# SCH_Flight-Computer-V5_2024-08-19.net
KiCad netlist of a schematic drawn in EasyEDA
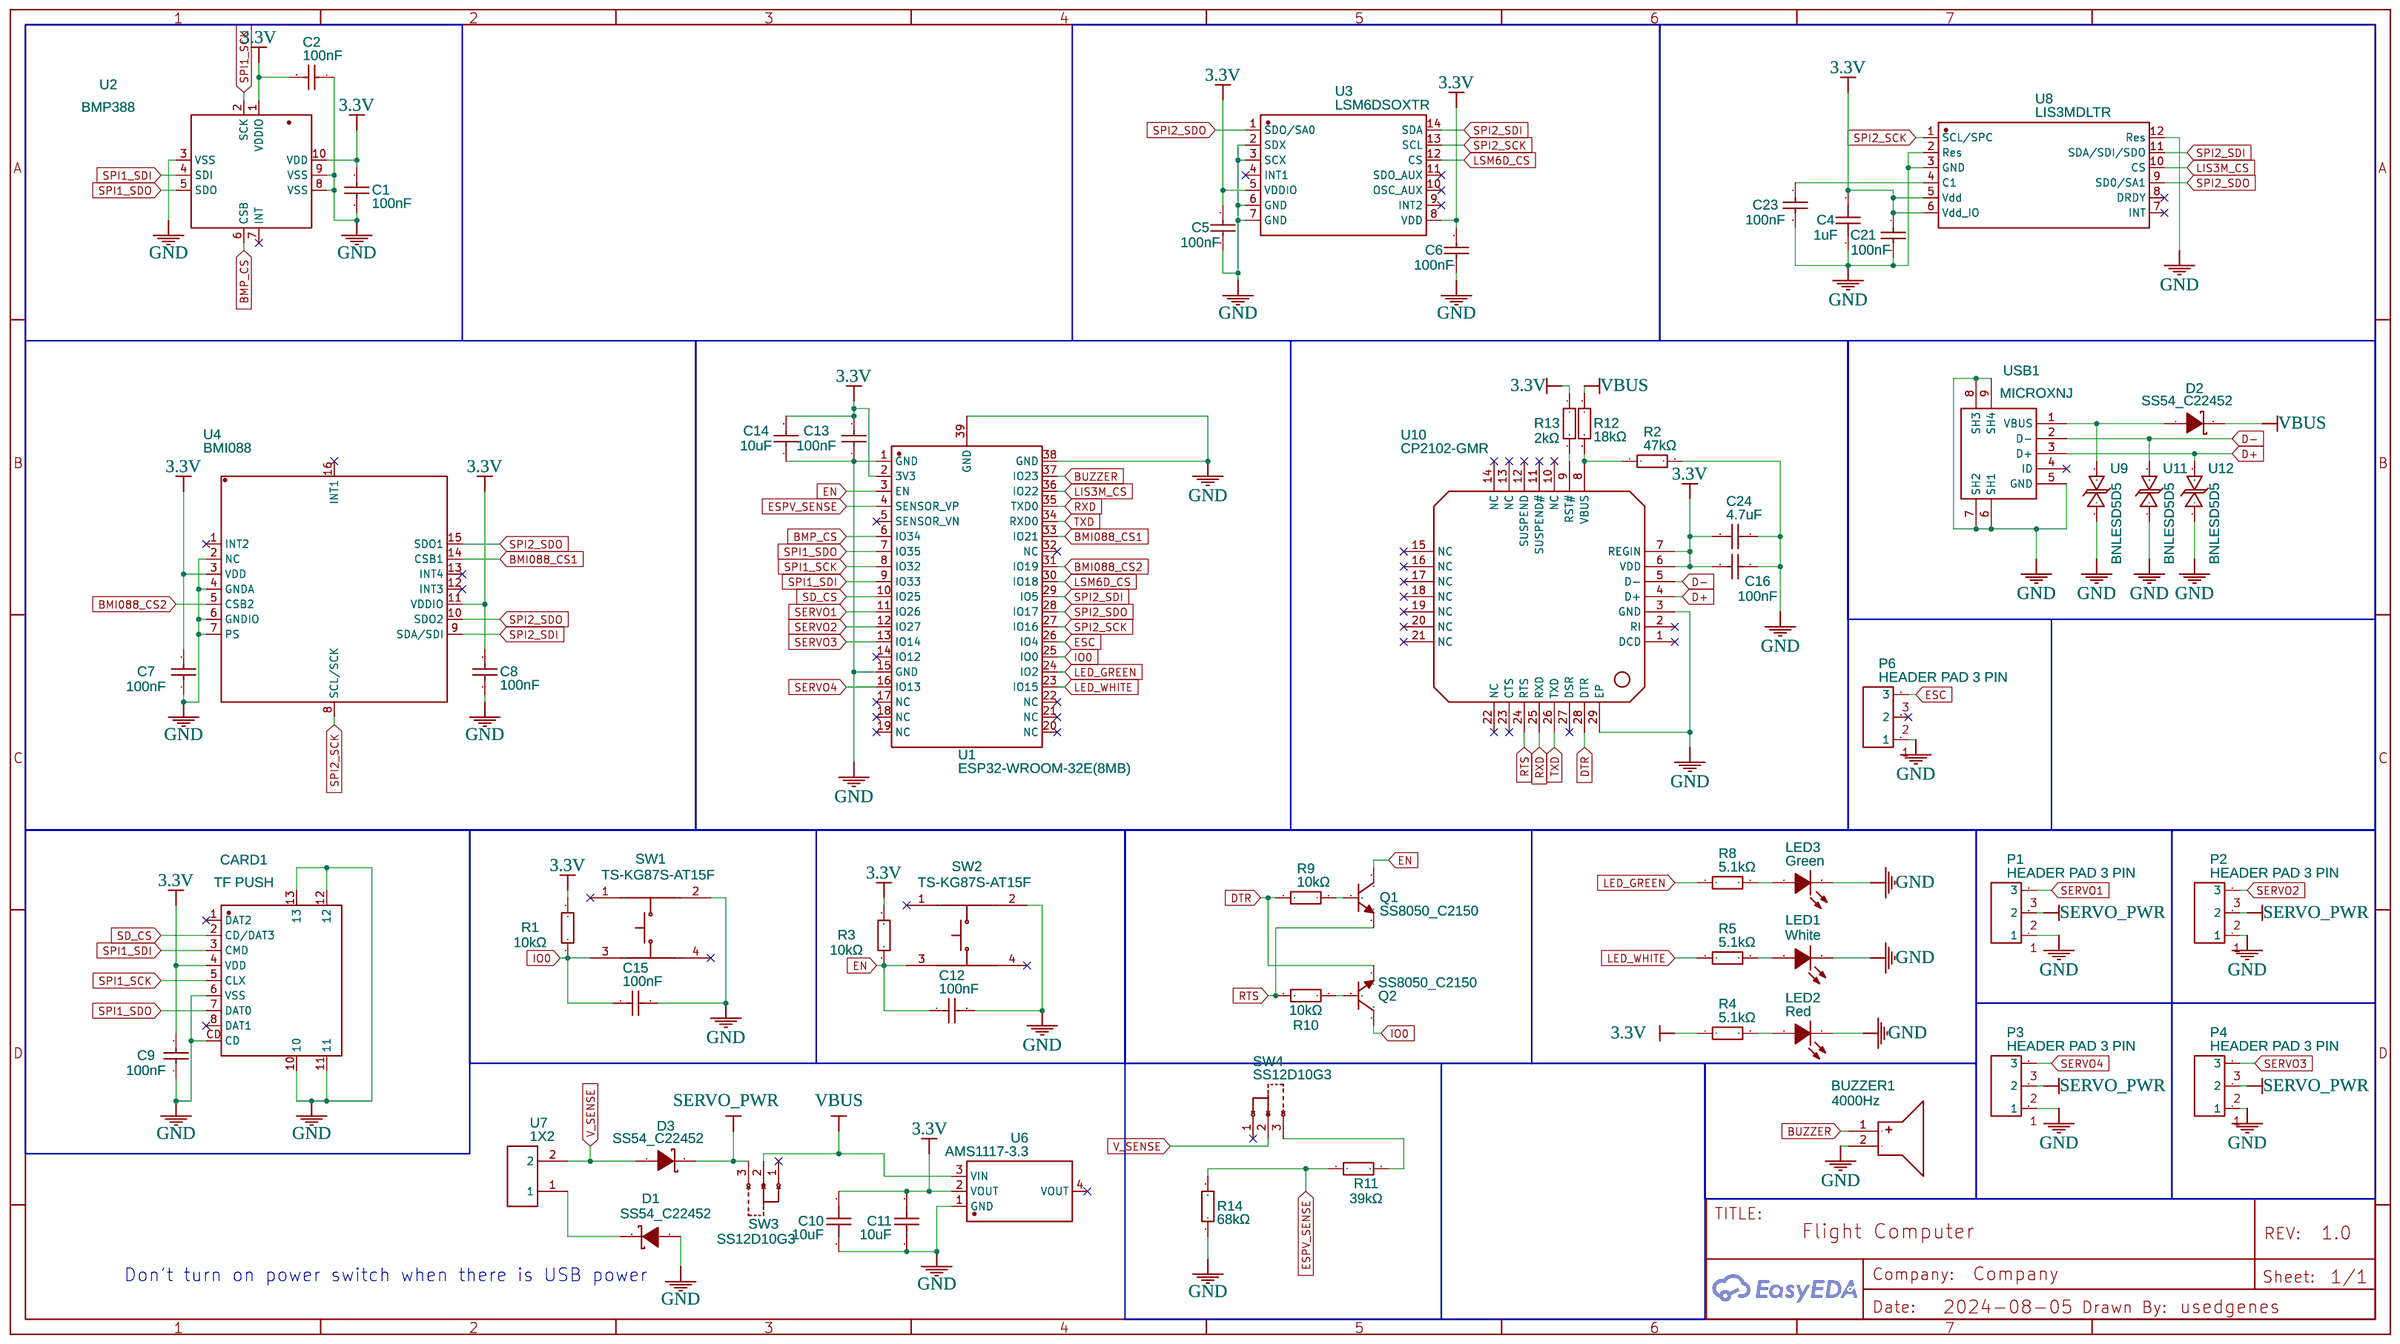
[diagram p0: schematic sheet]

(export (version "E")
  (design (tool "Eeschema 10.0.6"))
  (components
    (comp (ref "BUZZER1")
      (value "4000Hz")
      (fields
        (field (name "Manufacturer Part") "SKY-1475-0540-45P7.6")
        (field (name "Manufacturer") "S&S(海旭)")
      )
      (libsource (lib "") (part "SKY-1475-0540-45P7.6"))
    )
    (comp (ref "C1")
      (value "100nF")
      (fields
        (field (name "Manufacturer Part") "CL05B104KO5NNNC")
        (field (name "Manufacturer") "SAMSUNG(三星)")
      )
      (libsource (lib "") (part "CL05B104KO5NNNC_1"))
    )
    (comp (ref "C2")
      (value "100nF")
      (fields
        (field (name "Manufacturer Part") "CL05B104KO5NNNC")
        (field (name "Manufacturer") "SAMSUNG(三星)")
      )
      (libsource (lib "") (part "CL05B104KO5NNNC_2"))
    )
    (comp (ref "C4")
      (value "1uF")
      (fields
        (field (name "Manufacturer Part") "CL05A105KA5NQNC")
        (field (name "Manufacturer") "SAMSUNG(三星)")
      )
      (libsource (lib "") (part "CL05A105KA5NQNC"))
    )
    (comp (ref "C5")
      (value "100nF")
      (fields
        (field (name "Manufacturer Part") "CL05B104KO5NNNC")
        (field (name "Manufacturer") "SAMSUNG(三星)")
      )
      (libsource (lib "") (part "CL05B104KO5NNNC_1"))
    )
    (comp (ref "C6")
      (value "100nF")
      (fields
        (field (name "Manufacturer Part") "CL05B104KO5NNNC")
        (field (name "Manufacturer") "SAMSUNG(三星)")
      )
      (libsource (lib "") (part "CL05B104KO5NNNC_1"))
    )
    (comp (ref "C7")
      (value "100nF")
      (fields
        (field (name "Manufacturer Part") "CL05B104KO5NNNC")
        (field (name "Manufacturer") "SAMSUNG(三星)")
      )
      (libsource (lib "") (part "CL05B104KO5NNNC_1"))
    )
    (comp (ref "C8")
      (value "100nF")
      (fields
        (field (name "Manufacturer Part") "CL05B104KO5NNNC")
        (field (name "Manufacturer") "SAMSUNG(三星)")
      )
      (libsource (lib "") (part "CL05B104KO5NNNC_1"))
    )
    (comp (ref "C9")
      (value "100nF")
      (fields
        (field (name "Manufacturer Part") "CL05B104KO5NNNC")
        (field (name "Manufacturer") "SAMSUNG(三星)")
      )
      (libsource (lib "") (part "CL05B104KO5NNNC_1"))
    )
    (comp (ref "C10")
      (value "10uF")
      (fields
        (field (name "Manufacturer Part") "CL10A106KP8NNNC")
        (field (name "Manufacturer") "SAMSUNG(三星)")
      )
      (libsource (lib "") (part "CL10A106KP8NNNC"))
    )
    (comp (ref "C11")
      (value "10uF")
      (fields
        (field (name "Manufacturer Part") "CL10A106KP8NNNC")
        (field (name "Manufacturer") "SAMSUNG(三星)")
      )
      (libsource (lib "") (part "CL10A106KP8NNNC"))
    )
    (comp (ref "C12")
      (value "100nF")
      (fields
        (field (name "Manufacturer Part") "CL05B104KO5NNNC")
        (field (name "Manufacturer") "SAMSUNG(三星)")
      )
      (libsource (lib "") (part "CL05B104KO5NNNC"))
    )
    (comp (ref "C13")
      (value "100nF")
      (fields
        (field (name "Manufacturer Part") "CL05B104KO5NNNC")
        (field (name "Manufacturer") "SAMSUNG(三星)")
      )
      (libsource (lib "") (part "CL05B104KO5NNNC_1"))
    )
    (comp (ref "C14")
      (value "10uF")
      (fields
        (field (name "Manufacturer Part") "CL05A106MQ5NUNC")
        (field (name "Manufacturer") "SAMSUNG(三星)")
      )
      (libsource (lib "") (part "CL05A106MQ5NUNC"))
    )
    (comp (ref "C15")
      (value "100nF")
      (fields
        (field (name "Manufacturer Part") "CL05B104KO5NNNC")
        (field (name "Manufacturer") "SAMSUNG(三星)")
      )
      (libsource (lib "") (part "CL05B104KO5NNNC"))
    )
    (comp (ref "C16")
      (value "100nF")
      (fields
        (field (name "Manufacturer Part") "CL05B104KO5NNNC")
        (field (name "Manufacturer") "SAMSUNG(三星)")
      )
      (libsource (lib "") (part "CL05B104KO5NNNC"))
    )
    (comp (ref "C21")
      (value "100nF")
      (fields
        (field (name "Manufacturer Part") "CL05B104KO5NNNC")
        (field (name "Manufacturer") "SAMSUNG(三星)")
      )
      (libsource (lib "") (part "CL05B104KO5NNNC_3"))
    )
    (comp (ref "C23")
      (value "100nF")
      (fields
        (field (name "Manufacturer Part") "CL05B104KO5NNNC")
        (field (name "Manufacturer") "SAMSUNG(三星)")
      )
      (libsource (lib "") (part "CL05B104KO5NNNC_3"))
    )
    (comp (ref "C24")
      (value "4.7uF")
      (fields
        (field (name "Manufacturer Part") "CL05A475MP5NRNC")
        (field (name "Manufacturer") "SAMSUNG(三星)")
      )
      (libsource (lib "") (part "CL05A475MP5NRNC"))
    )
    (comp (ref "CARD1")
      (value "TF PUSH")
      (fields (field (name "Manufacturer") "SHOU HAN(首韩)"))
      (libsource (lib "") (part "TF PUSH"))
    )
    (comp (ref "D1")
      (value "SS54_C22452")
      (fields (field (name "Manufacturer Part") "SS54") (field (name "Manufacturer") "MDD(辰达半导体)"))
      (libsource (lib "") (part "SS54_C22452_1"))
    )
    (comp (ref "D2")
      (value "SS54_C22452")
      (fields (field (name "Manufacturer Part") "SS54") (field (name "Manufacturer") "MDD(辰达半导体)"))
      (libsource (lib "") (part "SS54_C22452"))
    )
    (comp (ref "D3")
      (value "SS54_C22452")
      (fields (field (name "Manufacturer Part") "SS54") (field (name "Manufacturer") "MDD(辰达半导体)"))
      (libsource (lib "") (part "SS54_C22452"))
    )
    (comp (ref "LED1")
      (value "White")
      (fields (field (name "Manufacturer Part") "KT-0603白灯") (field (name "Manufacturer") "KENTO"))
      (libsource (lib "") (part "0603White light_C2290"))
    )
    (comp (ref "LED2")
      (value "Red")
      (fields (field (name "Manufacturer Part") "KT-0603R") (field (name "Manufacturer") "KENTO"))
      (libsource (lib "") (part "KT-0603R"))
    )
    (comp (ref "LED3")
      (value "Green")
      (fields (field (name "Manufacturer Part") "KT-0805G") (field (name "Manufacturer") "KENTO"))
      (libsource (lib "") (part "0805G (Green)"))
    )
    (comp (ref "P1")
      (value "HEADER PAD 3 PIN")
      (fields
        (field (name "Manufacturer Part") "Female headerHDR1X8-2.54")
        (field (name "Manufacturer") "BOOMELE")
      )
      (libsource (lib "") (part "HEADER PAD 3 PIN"))
    )
    (comp (ref "P2")
      (value "HEADER PAD 3 PIN")
      (fields
        (field (name "Manufacturer Part") "Female headerHDR1X8-2.54")
        (field (name "Manufacturer") "BOOMELE")
      )
      (libsource (lib "") (part "HEADER PAD 3 PIN"))
    )
    (comp (ref "P3")
      (value "HEADER PAD 3 PIN")
      (fields
        (field (name "Manufacturer Part") "Female headerHDR1X8-2.54")
        (field (name "Manufacturer") "BOOMELE")
      )
      (libsource (lib "") (part "HEADER PAD 3 PIN"))
    )
    (comp (ref "P4")
      (value "HEADER PAD 3 PIN")
      (fields
        (field (name "Manufacturer Part") "Female headerHDR1X8-2.54")
        (field (name "Manufacturer") "BOOMELE")
      )
      (libsource (lib "") (part "HEADER PAD 3 PIN"))
    )
    (comp (ref "P6")
      (value "HEADER PAD 3 PIN")
      (fields
        (field (name "Manufacturer Part") "Female headerHDR1X8-2.54")
        (field (name "Manufacturer") "BOOMELE")
      )
      (libsource (lib "") (part "HEADER PAD 3 PIN"))
    )
    (comp (ref "Q1")
      (value "SS8050_C2150")
      (fields (field (name "Manufacturer Part") "SS8050") (field (name "Manufacturer") "CJ(江苏长电/长晶)"))
      (libsource (lib "") (part "SS8050_C2150_1"))
    )
    (comp (ref "Q2")
      (value "SS8050_C2150")
      (fields (field (name "Manufacturer Part") "SS8050") (field (name "Manufacturer") "CJ(江苏长电/长晶)"))
      (libsource (lib "") (part "SS8050_C2150"))
    )
    (comp (ref "R1")
      (value "10kΩ")
      (fields
        (field (name "Manufacturer Part") "0603WAF1002T5E")
        (field (name "Manufacturer") "UNI-ROYAL(厚声)")
      )
      (libsource (lib "") (part "0603WAF1002T5E_1"))
    )
    (comp (ref "R2")
      (value "47kΩ")
      (fields
        (field (name "Manufacturer Part") "0402WGF4702TCE")
        (field (name "Manufacturer") "UNI-ROYAL(厚声)")
      )
      (libsource (lib "") (part "0402WGF4702TCE"))
    )
    (comp (ref "R3")
      (value "10kΩ")
      (fields
        (field (name "Manufacturer Part") "0603WAF1002T5E")
        (field (name "Manufacturer") "UNI-ROYAL(厚声)")
      )
      (libsource (lib "") (part "0603WAF1002T5E_1"))
    )
    (comp (ref "R4")
      (value "5.1kΩ")
      (fields
        (field (name "Manufacturer Part") "0402WGF5101TCE")
        (field (name "Manufacturer") "UNI-ROYAL(厚声)")
      )
      (libsource (lib "") (part "0402WGF5101TCE"))
    )
    (comp (ref "R5")
      (value "5.1kΩ")
      (fields
        (field (name "Manufacturer Part") "0402WGF5101TCE")
        (field (name "Manufacturer") "UNI-ROYAL(厚声)")
      )
      (libsource (lib "") (part "0402WGF5101TCE"))
    )
    (comp (ref "R8")
      (value "5.1kΩ")
      (fields
        (field (name "Manufacturer Part") "0402WGF5101TCE")
        (field (name "Manufacturer") "UNI-ROYAL(厚声)")
      )
      (libsource (lib "") (part "0402WGF5101TCE"))
    )
    (comp (ref "R9")
      (value "10kΩ")
      (fields
        (field (name "Manufacturer Part") "0603WAF1002T5E")
        (field (name "Manufacturer") "UNI-ROYAL(厚声)")
      )
      (libsource (lib "") (part "0603WAF1002T5E_2"))
    )
    (comp (ref "R10")
      (value "10kΩ")
      (fields
        (field (name "Manufacturer Part") "0603WAF1002T5E")
        (field (name "Manufacturer") "UNI-ROYAL(厚声)")
      )
      (libsource (lib "") (part "0603WAF1002T5E"))
    )
    (comp (ref "R11")
      (value "39kΩ")
      (fields
        (field (name "Manufacturer Part") "0603WAF3902T5E")
        (field (name "Manufacturer") "UNI-ROYAL(厚声)")
      )
      (libsource (lib "") (part "0603WAF3902T5E"))
    )
    (comp (ref "R12")
      (value "18kΩ")
      (fields
        (field (name "Manufacturer Part") "0603WAF1802T5E")
        (field (name "Manufacturer") "UNI-ROYAL(厚声)")
      )
      (libsource (lib "") (part "0603WAF1802T5E"))
    )
    (comp (ref "R13")
      (value "2kΩ")
      (fields
        (field (name "Manufacturer Part") "0402WGF2001TCE")
        (field (name "Manufacturer") "UNI-ROYAL(厚声)")
      )
      (libsource (lib "") (part "0402WGF2001TCE"))
    )
    (comp (ref "R14")
      (value "68kΩ")
      (fields
        (field (name "Manufacturer Part") "0603WAF6802T5E")
        (field (name "Manufacturer") "UNI-ROYAL(厚声)")
      )
      (libsource (lib "") (part "0603WAF6802T5E"))
    )
    (comp (ref "SW1")
      (value "TS-KG87S-AT15F")
      (fields (field (name "Manufacturer") "HANBO(汉博)"))
      (libsource (lib "") (part "TS-KG87S-AT15F"))
    )
    (comp (ref "SW2")
      (value "TS-KG87S-AT15F")
      (fields (field (name "Manufacturer") "HANBO(汉博)"))
      (libsource (lib "") (part "TS-KG87S-AT15F"))
    )
    (comp (ref "SW3")
      (value "SS12D10G3")
      (fields (field (name "Manufacturer") "SHOU HAN(首韩)"))
      (libsource (lib "") (part "SS12D10G3_1"))
    )
    (comp (ref "SW4")
      (value "SS12D10G3")
      (fields (field (name "Manufacturer") "SHOU HAN(首韩)"))
      (libsource (lib "") (part "SS12D10G3"))
    )
    (comp (ref "U1")
      (value "ESP32-WROOM-32E(8MB)")
      (fields
        (field (name "Manufacturer Part") "ESP32-WROOM-32E-N8")
        (field (name "Manufacturer") "ESPRESSIF(乐鑫)")
      )
      (libsource (lib "") (part "ESP32-WROOM-32E(8MB)"))
    )
    (comp (ref "U2")
      (value "BMP388")
      (fields (field (name "Manufacturer") "Bosch(博世)"))
      (libsource (lib "") (part "BMP388"))
    )
    (comp (ref "U3")
      (value "LSM6DSOXTR")
      (fields (field (name "Manufacturer") "ST(意法半导体)"))
      (libsource (lib "") (part "LSM6DSOXTR"))
    )
    (comp (ref "U4")
      (value "BMI088")
      (fields (field (name "Manufacturer") "Bosch(博世)"))
      (libsource (lib "") (part "BMI088"))
    )
    (comp (ref "U6")
      (value "AMS1117-3.3")
      (fields (field (name "Manufacturer") "AMS"))
      (libsource (lib "") (part "AMS1117-3.3"))
    )
    (comp (ref "U7") (value "1X2") (libsource (lib "") (part "1X2")))
    (comp (ref "U8")
      (value "LIS3MDLTR")
      (fields (field (name "Manufacturer") "ST(意法半导体)"))
      (libsource (lib "") (part "LIS3MDLTR"))
    )
    (comp (ref "U9")
      (value "BNLESD5D5")
      (fields
        (field (name "Manufacturer Part") "BNLESD5D5.0CT1G")
        (field (name "Manufacturer") "BORN(伯恩半导体)")
      )
      (libsource (lib "") (part "BNLESD5D5.0CT1G"))
    )
    (comp (ref "U10")
      (value "CP2102-GMR")
      (fields (field (name "Manufacturer") "SKYWORKS/SILICON LABS(芯科)"))
      (libsource (lib "") (part "CP2102-GMR"))
    )
    (comp (ref "U11")
      (value "BNLESD5D5")
      (fields
        (field (name "Manufacturer Part") "BNLESD5D5.0CT1G")
        (field (name "Manufacturer") "BORN(伯恩半导体)")
      )
      (libsource (lib "") (part "BNLESD5D5.0CT1G"))
    )
    (comp (ref "U12")
      (value "BNLESD5D5")
      (fields
        (field (name "Manufacturer Part") "BNLESD5D5.0CT1G")
        (field (name "Manufacturer") "BORN(伯恩半导体)")
      )
      (libsource (lib "") (part "BNLESD5D5.0CT1G"))
    )
    (comp (ref "USB1")
      (value "MICROXNJ")
      (fields (field (name "Manufacturer Part") "MicroXNJ") (field (name "Manufacturer") "SHOU HAN(首韩)"))
      (libsource (lib "") (part "MICROXNJ"))
    )
  )
  (nets
    (net (code "1") (name "3.3V") (class "Default")
      (node (ref "C1") (pin "2") (pinfunction "2_2") (pintype "input"))
      (node (ref "C10") (pin "2") (pinfunction "2_2") (pintype "unspecified"))
      (node (ref "C11") (pin "2") (pinfunction "2_2") (pintype "unspecified"))
      (node (ref "C13") (pin "2") (pinfunction "2_2") (pintype "input"))
      (node (ref "C14") (pin "2") (pinfunction "2_2") (pintype "input"))
      (node (ref "C16") (pin "1") (pinfunction "1_1") (pintype "input"))
      (node (ref "C2") (pin "2") (pinfunction "2_2") (pintype "input"))
      (node (ref "C21") (pin "1") (pinfunction "1_1") (pintype "input"))
      (node (ref "C24") (pin "1") (pinfunction "1_1") (pintype "input"))
      (node (ref "C4") (pin "2") (pinfunction "2_2") (pintype "unspecified"))
      (node (ref "C5") (pin "2") (pinfunction "2_2") (pintype "input"))
      (node (ref "C6") (pin "2") (pinfunction "2_2") (pintype "input"))
      (node (ref "C7") (pin "2") (pinfunction "2_2") (pintype "input"))
      (node (ref "C8") (pin "2") (pinfunction "2_2") (pintype "input"))
      (node (ref "C9") (pin "2") (pinfunction "2_2") (pintype "input"))
      (node (ref "CARD1") (pin "4") (pinfunction "VDD_4") (pintype "unspecified"))
      (node (ref "R1") (pin "2") (pinfunction "2_2") (pintype "input"))
      (node (ref "R13") (pin "1") (pinfunction "1_1") (pintype "input"))
      (node (ref "R3") (pin "2") (pinfunction "2_2") (pintype "input"))
      (node (ref "R4") (pin "1") (pinfunction "1_1") (pintype "input"))
      (node (ref "U1") (pin "2") (pinfunction "3V3_2") (pintype "unspecified"))
      (node (ref "U10") (pin "6") (pinfunction "VDD_6") (pintype "unspecified"))
      (node (ref "U10") (pin "7") (pinfunction "REGIN_7") (pintype "unspecified"))
      (node (ref "U2") (pin "1") (pinfunction "VDDIO_1") (pintype "unspecified"))
      (node (ref "U2") (pin "10") (pinfunction "VDD_10") (pintype "unspecified"))
      (node (ref "U3") (pin "5") (pinfunction "VDDIO_5") (pintype "unspecified"))
      (node (ref "U3") (pin "8") (pinfunction "VDD_8") (pintype "unspecified"))
      (node (ref "U4") (pin "11") (pinfunction "VDDIO_11") (pintype "unspecified"))
      (node (ref "U4") (pin "3") (pinfunction "VDD_3") (pintype "unspecified"))
      (node (ref "U6") (pin "2") (pinfunction "VOUT_2") (pintype "unspecified"))
      (node (ref "U8") (pin "5") (pinfunction "Vdd_5") (pintype "unspecified"))
      (node (ref "U8") (pin "6") (pinfunction "Vdd_IO_6") (pintype "unspecified"))
    )
    (net (code "2") (name "BMI088_CS1") (class "Default")
      (node (ref "U1") (pin "33") (pinfunction "IO21_33") (pintype "unspecified"))
      (node (ref "U4") (pin "14") (pinfunction "CSB1_14") (pintype "unspecified"))
    )
    (net (code "3") (name "BMI088_CS2") (class "Default")
      (node (ref "U1") (pin "31") (pinfunction "IO19_31") (pintype "unspecified"))
      (node (ref "U4") (pin "5") (pinfunction "CSB2_5") (pintype "unspecified"))
    )
    (net (code "4") (name "BMP_CS") (class "Default")
      (node (ref "U1") (pin "6") (pinfunction "IO34_6") (pintype "unspecified"))
      (node (ref "U2") (pin "6") (pinfunction "CSB_6") (pintype "unspecified"))
    )
    (net (code "5") (name "BUZZER") (class "Default")
      (node (ref "BUZZER1") (pin "1") (pinfunction "+_1") (pintype "unspecified"))
      (node (ref "U1") (pin "37") (pinfunction "IO23_37") (pintype "unspecified"))
    )
    (net (code "6") (name "D+") (class "Default")
      (node (ref "U10") (pin "4") (pinfunction "D+_4") (pintype "unspecified"))
      (node (ref "U12") (pin "2") (pinfunction "2_2") (pintype "unspecified"))
      (node (ref "USB1") (pin "3") (pinfunction "D+_3") (pintype "unspecified"))
    )
    (net (code "7") (name "D-") (class "Default")
      (node (ref "U10") (pin "5") (pinfunction "D-_5") (pintype "unspecified"))
      (node (ref "U11") (pin "2") (pinfunction "2_2") (pintype "unspecified"))
      (node (ref "USB1") (pin "2") (pinfunction "D-_2") (pintype "unspecified"))
    )
    (net (code "8") (name "DTR") (class "Default")
      (node (ref "Q2") (pin "2") (pinfunction "E_2") (pintype "unspecified"))
      (node (ref "R9") (pin "2") (pinfunction "2_2") (pintype "input"))
      (node (ref "U10") (pin "28") (pinfunction "DTR_28") (pintype "unspecified"))
    )
    (net (code "9") (name "EN") (class "Default")
      (node (ref "C12") (pin "1") (pinfunction "1_1") (pintype "input"))
      (node (ref "Q1") (pin "3") (pinfunction "C_3") (pintype "unspecified"))
      (node (ref "R3") (pin "1") (pinfunction "1_1") (pintype "input"))
      (node (ref "SW2") (pin "3") (pinfunction "3_3") (pintype "unspecified"))
      (node (ref "U1") (pin "3") (pinfunction "EN_3") (pintype "unspecified"))
    )
    (net (code "10") (name "ESC") (class "Default")
      (node (ref "P6") (pin "3") (pinfunction "3_3") (pintype "unspecified"))
      (node (ref "U1") (pin "26") (pinfunction "IO4_26") (pintype "unspecified"))
    )
    (net (code "11") (name "ESPV_SENSE") (class "Default")
      (node (ref "R11") (pin "1") (pinfunction "1_1") (pintype "input"))
      (node (ref "R14") (pin "2") (pinfunction "2_2") (pintype "input"))
      (node (ref "U1") (pin "4") (pinfunction "SENSOR_VP_4") (pintype "unspecified"))
    )
    (net (code "12") (name "GND") (class "Default")
      (node (ref "BUZZER1") (pin "2") (pinfunction "-_2") (pintype "unspecified"))
      (node (ref "C1") (pin "1") (pinfunction "1_1") (pintype "input"))
      (node (ref "C10") (pin "1") (pinfunction "1_1") (pintype "unspecified"))
      (node (ref "C11") (pin "1") (pinfunction "1_1") (pintype "unspecified"))
      (node (ref "C12") (pin "2") (pinfunction "2_2") (pintype "input"))
      (node (ref "C13") (pin "1") (pinfunction "1_1") (pintype "input"))
      (node (ref "C14") (pin "1") (pinfunction "1_1") (pintype "input"))
      (node (ref "C15") (pin "2") (pinfunction "2_2") (pintype "input"))
      (node (ref "C16") (pin "2") (pinfunction "2_2") (pintype "input"))
      (node (ref "C2") (pin "1") (pinfunction "1_1") (pintype "input"))
      (node (ref "C21") (pin "2") (pinfunction "2_2") (pintype "input"))
      (node (ref "C23") (pin "2") (pinfunction "2_2") (pintype "input"))
      (node (ref "C24") (pin "2") (pinfunction "2_2") (pintype "input"))
      (node (ref "C4") (pin "1") (pinfunction "1_1") (pintype "unspecified"))
      (node (ref "C5") (pin "1") (pinfunction "1_1") (pintype "input"))
      (node (ref "C6") (pin "1") (pinfunction "1_1") (pintype "input"))
      (node (ref "C7") (pin "1") (pinfunction "1_1") (pintype "input"))
      (node (ref "C8") (pin "1") (pinfunction "1_1") (pintype "input"))
      (node (ref "C9") (pin "1") (pinfunction "1_1") (pintype "input"))
      (node (ref "CARD1") (pin "10") (pinfunction "10_10") (pintype "unspecified"))
      (node (ref "CARD1") (pin "11") (pinfunction "11_11") (pintype "unspecified"))
      (node (ref "CARD1") (pin "12") (pinfunction "12_12") (pintype "unspecified"))
      (node (ref "CARD1") (pin "13") (pinfunction "13_13") (pintype "unspecified"))
      (node (ref "CARD1") (pin "6") (pinfunction "VSS_6") (pintype "unspecified"))
      (node (ref "CARD1") (pin "CD") (pinfunction "CD_CD") (pintype "unspecified"))
      (node (ref "D1") (pin "1") (pinfunction "A_1") (pintype "unspecified"))
      (node (ref "LED1") (pin "2") (pinfunction "K_2") (pintype "unspecified"))
      (node (ref "LED2") (pin "1") (pinfunction "K_1") (pintype "unspecified"))
      (node (ref "LED3") (pin "2") (pinfunction "K_2") (pintype "unspecified"))
      (node (ref "P1") (pin "1") (pinfunction "1_1") (pintype "unspecified"))
      (node (ref "P2") (pin "1") (pinfunction "1_1") (pintype "unspecified"))
      (node (ref "P3") (pin "1") (pinfunction "1_1") (pintype "unspecified"))
      (node (ref "P4") (pin "1") (pinfunction "1_1") (pintype "unspecified"))
      (node (ref "P6") (pin "1") (pinfunction "1_1") (pintype "unspecified"))
      (node (ref "R14") (pin "1") (pinfunction "1_1") (pintype "input"))
      (node (ref "R2") (pin "2") (pinfunction "2_2") (pintype "input"))
      (node (ref "SW1") (pin "2") (pinfunction "2_2") (pintype "unspecified"))
      (node (ref "SW2") (pin "2") (pinfunction "2_2") (pintype "unspecified"))
      (node (ref "U1") (pin "1") (pinfunction "GND_1") (pintype "unspecified"))
      (node (ref "U1") (pin "15") (pinfunction "GND_15") (pintype "unspecified"))
      (node (ref "U1") (pin "38") (pinfunction "GND_38") (pintype "unspecified"))
      (node (ref "U1") (pin "39") (pinfunction "GND_39") (pintype "unspecified"))
      (node (ref "U10") (pin "29") (pinfunction "EP_29") (pintype "unspecified"))
      (node (ref "U10") (pin "3") (pinfunction "GND_3") (pintype "unspecified"))
      (node (ref "U11") (pin "1") (pinfunction "1_1") (pintype "unspecified"))
      (node (ref "U12") (pin "1") (pinfunction "1_1") (pintype "unspecified"))
      (node (ref "U2") (pin "3") (pinfunction "VSS_3") (pintype "unspecified"))
      (node (ref "U2") (pin "8") (pinfunction "VSS_8") (pintype "unspecified"))
      (node (ref "U2") (pin "9") (pinfunction "VSS_9") (pintype "unspecified"))
      (node (ref "U3") (pin "2") (pinfunction "SDX_2") (pintype "unspecified"))
      (node (ref "U3") (pin "3") (pinfunction "SCX_3") (pintype "unspecified"))
      (node (ref "U3") (pin "6") (pinfunction "GND_6") (pintype "unspecified"))
      (node (ref "U3") (pin "7") (pinfunction "GND_7") (pintype "unspecified"))
      (node (ref "U4") (pin "2") (pinfunction "NC_2") (pintype "unspecified"))
      (node (ref "U4") (pin "4") (pinfunction "GNDA_4") (pintype "unspecified"))
      (node (ref "U4") (pin "6") (pinfunction "GNDIO_6") (pintype "unspecified"))
      (node (ref "U4") (pin "7") (pinfunction "PS_7") (pintype "unspecified"))
      (node (ref "U6") (pin "1") (pinfunction "GND_1") (pintype "unspecified"))
      (node (ref "U8") (pin "12") (pinfunction "Res_12") (pintype "unspecified"))
      (node (ref "U8") (pin "2") (pinfunction "Res_2") (pintype "unspecified"))
      (node (ref "U8") (pin "3") (pinfunction "GND_3") (pintype "unspecified"))
      (node (ref "U9") (pin "1") (pinfunction "1_1") (pintype "unspecified"))
      (node (ref "USB1") (pin "5") (pinfunction "GND_5") (pintype "unspecified"))
      (node (ref "USB1") (pin "6") (pinfunction "SH1_6") (pintype "unspecified"))
      (node (ref "USB1") (pin "7") (pinfunction "SH2_7") (pintype "unspecified"))
      (node (ref "USB1") (pin "8") (pinfunction "SH3_8") (pintype "unspecified"))
      (node (ref "USB1") (pin "9") (pinfunction "SH4_9") (pintype "unspecified"))
    )
    (net (code "13") (name "IO0") (class "Default")
      (node (ref "C15") (pin "1") (pinfunction "1_1") (pintype "input"))
      (node (ref "Q2") (pin "3") (pinfunction "C_3") (pintype "unspecified"))
      (node (ref "R1") (pin "1") (pinfunction "1_1") (pintype "input"))
      (node (ref "SW1") (pin "3") (pinfunction "3_3") (pintype "unspecified"))
      (node (ref "U1") (pin "25") (pinfunction "IO0_25") (pintype "unspecified"))
    )
    (net (code "14") (name "LED_GREEN") (class "Default")
      (node (ref "R8") (pin "1") (pinfunction "1_1") (pintype "input"))
      (node (ref "U1") (pin "24") (pinfunction "IO2_24") (pintype "unspecified"))
    )
    (net (code "15") (name "LED_WHITE") (class "Default")
      (node (ref "R5") (pin "1") (pinfunction "1_1") (pintype "input"))
      (node (ref "U1") (pin "23") (pinfunction "IO15_23") (pintype "unspecified"))
    )
    (net (code "16") (name "LIS3M_CS") (class "Default")
      (node (ref "U1") (pin "36") (pinfunction "IO22_36") (pintype "unspecified"))
      (node (ref "U8") (pin "10") (pinfunction "CS_10") (pintype "unspecified"))
    )
    (net (code "17") (name "LSM6D_CS") (class "Default")
      (node (ref "U1") (pin "30") (pinfunction "IO18_30") (pintype "unspecified"))
      (node (ref "U3") (pin "12") (pinfunction "CS_12") (pintype "unspecified"))
    )
    (net (code "18") (name "Net-(D1-K)") (class "Default")
      (node (ref "D1") (pin "2") (pinfunction "K_2") (pintype "unspecified"))
      (node (ref "U7") (pin "1") (pinfunction "1_1") (pintype "unspecified"))
    )
    (net (code "19") (name "Net-(D2-A)") (class "Default")
      (node (ref "D2") (pin "1") (pinfunction "A_1") (pintype "unspecified"))
      (node (ref "U9") (pin "2") (pinfunction "2_2") (pintype "unspecified"))
      (node (ref "USB1") (pin "1") (pinfunction "VBUS_1") (pintype "unspecified"))
    )
    (net (code "20") (name "Net-(LED1-A)") (class "Default")
      (node (ref "LED1") (pin "1") (pinfunction "A_1") (pintype "unspecified"))
      (node (ref "R5") (pin "2") (pinfunction "2_2") (pintype "input"))
    )
    (net (code "21") (name "Net-(LED2-A)") (class "Default")
      (node (ref "LED2") (pin "2") (pinfunction "A_2") (pintype "unspecified"))
      (node (ref "R4") (pin "2") (pinfunction "2_2") (pintype "input"))
    )
    (net (code "22") (name "Net-(LED3-A)") (class "Default")
      (node (ref "LED3") (pin "1") (pinfunction "A_1") (pintype "unspecified"))
      (node (ref "R8") (pin "2") (pinfunction "2_2") (pintype "input"))
    )
    (net (code "23") (name "Net-(Q1-B)") (class "Default")
      (node (ref "Q1") (pin "1") (pinfunction "B_1") (pintype "unspecified"))
      (node (ref "R9") (pin "1") (pinfunction "1_1") (pintype "input"))
    )
    (net (code "24") (name "Net-(Q2-B)") (class "Default")
      (node (ref "Q2") (pin "1") (pinfunction "B_1") (pintype "unspecified"))
      (node (ref "R10") (pin "2") (pinfunction "2_2") (pintype "input"))
    )
    (net (code "25") (name "Net-(R11-Pad2)") (class "Default")
      (node (ref "R11") (pin "2") (pinfunction "2_2") (pintype "input"))
      (node (ref "SW4") (pin "3") (pinfunction "3_3") (pintype "unspecified"))
    )
    (net (code "26") (name "Net-(U8-C1)") (class "Default")
      (node (ref "C23") (pin "1") (pinfunction "1_1") (pintype "input"))
      (node (ref "U8") (pin "4") (pinfunction "C1_4") (pintype "unspecified"))
    )
    (net (code "27") (name "Net-(U10-RST#)") (class "Default")
      (node (ref "R13") (pin "2") (pinfunction "2_2") (pintype "input"))
      (node (ref "U10") (pin "9") (pinfunction "RST#_9") (pintype "unspecified"))
    )
    (net (code "28") (name "Net-(U10-VBUS)") (class "Default")
      (node (ref "R12") (pin "2") (pinfunction "2_2") (pintype "input"))
      (node (ref "R2") (pin "1") (pinfunction "1_1") (pintype "input"))
      (node (ref "U10") (pin "8") (pinfunction "VBUS_8") (pintype "unspecified"))
    )
    (net (code "29") (name "RTS") (class "Default")
      (node (ref "Q1") (pin "2") (pinfunction "E_2") (pintype "unspecified"))
      (node (ref "R10") (pin "1") (pinfunction "1_1") (pintype "input"))
      (node (ref "U10") (pin "24") (pinfunction "RTS_24") (pintype "unspecified"))
    )
    (net (code "30") (name "RXD") (class "Default")
      (node (ref "U1") (pin "35") (pinfunction "TXD0_35") (pintype "unspecified"))
      (node (ref "U10") (pin "25") (pinfunction "RXD_25") (pintype "unspecified"))
    )
    (net (code "31") (name "SD_CS") (class "Default")
      (node (ref "CARD1") (pin "2") (pinfunction "CD/DAT3_2") (pintype "unspecified"))
      (node (ref "U1") (pin "10") (pinfunction "IO25_10") (pintype "unspecified"))
    )
    (net (code "32") (name "SERVO1") (class "Default")
      (node (ref "P1") (pin "3") (pinfunction "3_3") (pintype "unspecified"))
      (node (ref "U1") (pin "11") (pinfunction "IO26_11") (pintype "unspecified"))
    )
    (net (code "33") (name "SERVO2") (class "Default")
      (node (ref "P2") (pin "3") (pinfunction "3_3") (pintype "unspecified"))
      (node (ref "U1") (pin "12") (pinfunction "IO27_12") (pintype "unspecified"))
    )
    (net (code "34") (name "SERVO3") (class "Default")
      (node (ref "P4") (pin "3") (pinfunction "3_3") (pintype "unspecified"))
      (node (ref "U1") (pin "13") (pinfunction "IO14_13") (pintype "unspecified"))
    )
    (net (code "35") (name "SERVO4") (class "Default")
      (node (ref "P3") (pin "3") (pinfunction "3_3") (pintype "unspecified"))
      (node (ref "U1") (pin "16") (pinfunction "IO13_16") (pintype "unspecified"))
    )
    (net (code "36") (name "SERVO_PWR") (class "Default")
      (node (ref "D3") (pin "2") (pinfunction "K_2") (pintype "unspecified"))
      (node (ref "P1") (pin "2") (pinfunction "2_2") (pintype "unspecified"))
      (node (ref "P2") (pin "2") (pinfunction "2_2") (pintype "unspecified"))
      (node (ref "P3") (pin "2") (pinfunction "2_2") (pintype "unspecified"))
      (node (ref "P4") (pin "2") (pinfunction "2_2") (pintype "unspecified"))
      (node (ref "SW3") (pin "3") (pinfunction "3_3") (pintype "unspecified"))
    )
    (net (code "37") (name "SPI1_SCK") (class "Default")
      (node (ref "CARD1") (pin "5") (pinfunction "CLX_5") (pintype "unspecified"))
      (node (ref "U1") (pin "8") (pinfunction "IO32_8") (pintype "unspecified"))
      (node (ref "U2") (pin "2") (pinfunction "SCK_2") (pintype "unspecified"))
    )
    (net (code "38") (name "SPI1_SDI") (class "Default")
      (node (ref "CARD1") (pin "3") (pinfunction "CMD_3") (pintype "unspecified"))
      (node (ref "U1") (pin "9") (pinfunction "IO33_9") (pintype "unspecified"))
      (node (ref "U2") (pin "4") (pinfunction "SDI_4") (pintype "unspecified"))
    )
    (net (code "39") (name "SPI1_SDO") (class "Default")
      (node (ref "CARD1") (pin "7") (pinfunction "DAT0_7") (pintype "unspecified"))
      (node (ref "U1") (pin "7") (pinfunction "IO35_7") (pintype "unspecified"))
      (node (ref "U2") (pin "5") (pinfunction "SDO_5") (pintype "unspecified"))
    )
    (net (code "40") (name "SPI2_SCK") (class "Default")
      (node (ref "U1") (pin "27") (pinfunction "IO16_27") (pintype "unspecified"))
      (node (ref "U3") (pin "13") (pinfunction "SCL_13") (pintype "unspecified"))
      (node (ref "U4") (pin "8") (pinfunction "SCL/SCK_8") (pintype "unspecified"))
      (node (ref "U8") (pin "1") (pinfunction "SCL/SPC_1") (pintype "unspecified"))
    )
    (net (code "41") (name "SPI2_SDI") (class "Default")
      (node (ref "U1") (pin "29") (pinfunction "IO5_29") (pintype "unspecified"))
      (node (ref "U3") (pin "14") (pinfunction "SDA_14") (pintype "unspecified"))
      (node (ref "U4") (pin "9") (pinfunction "SDA/SDI_9") (pintype "unspecified"))
      (node (ref "U8") (pin "11") (pinfunction "SDA/SDI/SDO_11") (pintype "unspecified"))
    )
    (net (code "42") (name "SPI2_SDO") (class "Default")
      (node (ref "U1") (pin "28") (pinfunction "IO17_28") (pintype "unspecified"))
      (node (ref "U3") (pin "1") (pinfunction "SDO/SA0_1") (pintype "unspecified"))
      (node (ref "U4") (pin "10") (pinfunction "SDO2_10") (pintype "unspecified"))
      (node (ref "U4") (pin "15") (pinfunction "SDO1_15") (pintype "unspecified"))
      (node (ref "U8") (pin "9") (pinfunction "SD0/SA1_9") (pintype "unspecified"))
    )
    (net (code "43") (name "TXD") (class "Default")
      (node (ref "U1") (pin "34") (pinfunction "RXD0_34") (pintype "unspecified"))
      (node (ref "U10") (pin "26") (pinfunction "TXD_26") (pintype "unspecified"))
    )
    (net (code "44") (name "VBUS") (class "Default")
      (node (ref "D2") (pin "2") (pinfunction "K_2") (pintype "unspecified"))
      (node (ref "R12") (pin "1") (pinfunction "1_1") (pintype "input"))
      (node (ref "SW3") (pin "2") (pinfunction "2_2") (pintype "unspecified"))
      (node (ref "U6") (pin "3") (pinfunction "VIN_3") (pintype "unspecified"))
    )
    (net (code "45") (name "V_SENSE") (class "Default")
      (node (ref "D3") (pin "1") (pinfunction "A_1") (pintype "unspecified"))
      (node (ref "SW4") (pin "2") (pinfunction "2_2") (pintype "unspecified"))
      (node (ref "U7") (pin "2") (pinfunction "2_2") (pintype "unspecified"))
    )
    (net (code "46") (name "unconnected-(CARD1-DAT1-Pad8)") (class "Default")
      (node (ref "CARD1") (pin "8") (pinfunction "DAT1_8") (pintype "unspecified+no_connect"))
    )
    (net (code "47") (name "unconnected-(CARD1-DAT2-Pad1)") (class "Default")
      (node (ref "CARD1") (pin "1") (pinfunction "DAT2_1") (pintype "unspecified+no_connect"))
    )
    (net (code "48") (name "unconnected-(P6-Pad2)") (class "Default")
      (node (ref "P6") (pin "2") (pinfunction "2_2") (pintype "unspecified+no_connect"))
    )
    (net (code "49") (name "unconnected-(SW1-Pad1)") (class "Default")
      (node (ref "SW1") (pin "1") (pinfunction "1_1") (pintype "unspecified+no_connect"))
    )
    (net (code "50") (name "unconnected-(SW1-Pad4)") (class "Default")
      (node (ref "SW1") (pin "4") (pinfunction "4_4") (pintype "unspecified+no_connect"))
    )
    (net (code "51") (name "unconnected-(SW2-Pad1)") (class "Default")
      (node (ref "SW2") (pin "1") (pinfunction "1_1") (pintype "unspecified+no_connect"))
    )
    (net (code "52") (name "unconnected-(SW2-Pad4)") (class "Default")
      (node (ref "SW2") (pin "4") (pinfunction "4_4") (pintype "unspecified+no_connect"))
    )
    (net (code "53") (name "unconnected-(SW3-Pad1)") (class "Default")
      (node (ref "SW3") (pin "1") (pinfunction "1_1") (pintype "unspecified+no_connect"))
    )
    (net (code "54") (name "unconnected-(SW4-Pad1)") (class "Default")
      (node (ref "SW4") (pin "1") (pinfunction "1_1") (pintype "unspecified+no_connect"))
    )
    (net (code "55") (name "unconnected-(U1-IO12-Pad14)") (class "Default")
      (node (ref "U1") (pin "14") (pinfunction "IO12_14") (pintype "unspecified+no_connect"))
    )
    (net (code "56") (name "unconnected-(U1-NC-Pad17)") (class "Default")
      (node (ref "U1") (pin "17") (pinfunction "NC_17") (pintype "unspecified+no_connect"))
    )
    (net (code "57") (name "unconnected-(U1-NC-Pad18)") (class "Default")
      (node (ref "U1") (pin "18") (pinfunction "NC_18") (pintype "unspecified+no_connect"))
    )
    (net (code "58") (name "unconnected-(U1-NC-Pad19)") (class "Default")
      (node (ref "U1") (pin "19") (pinfunction "NC_19") (pintype "unspecified+no_connect"))
    )
    (net (code "59") (name "unconnected-(U1-NC-Pad20)") (class "Default")
      (node (ref "U1") (pin "20") (pinfunction "NC_20") (pintype "unspecified+no_connect"))
    )
    (net (code "60") (name "unconnected-(U1-NC-Pad21)") (class "Default")
      (node (ref "U1") (pin "21") (pinfunction "NC_21") (pintype "unspecified+no_connect"))
    )
    (net (code "61") (name "unconnected-(U1-NC-Pad22)") (class "Default")
      (node (ref "U1") (pin "22") (pinfunction "NC_22") (pintype "unspecified+no_connect"))
    )
    (net (code "62") (name "unconnected-(U1-NC-Pad32)") (class "Default")
      (node (ref "U1") (pin "32") (pinfunction "NC_32") (pintype "unspecified+no_connect"))
    )
    (net (code "63") (name "unconnected-(U1-SENSOR_VN-Pad5)") (class "Default")
      (node (ref "U1") (pin "5") (pinfunction "SENSOR_VN_5") (pintype "unspecified+no_connect"))
    )
    (net (code "64") (name "unconnected-(U2-INT-Pad7)") (class "Default")
      (node (ref "U2") (pin "7") (pinfunction "INT_7") (pintype "unspecified+no_connect"))
    )
    (net (code "65") (name "unconnected-(U3-INT1-Pad4)") (class "Default")
      (node (ref "U3") (pin "4") (pinfunction "INT1_4") (pintype "unspecified+no_connect"))
    )
    (net (code "66") (name "unconnected-(U3-INT2-Pad9)") (class "Default")
      (node (ref "U3") (pin "9") (pinfunction "INT2_9") (pintype "unspecified+no_connect"))
    )
    (net (code "67") (name "unconnected-(U3-OSC_AUX-Pad10)") (class "Default")
      (node (ref "U3") (pin "10") (pinfunction "OSC_AUX_10") (pintype "unspecified+no_connect"))
    )
    (net (code "68") (name "unconnected-(U3-SDO_AUX-Pad11)") (class "Default")
      (node (ref "U3") (pin "11") (pinfunction "SDO_AUX_11") (pintype "unspecified+no_connect"))
    )
    (net (code "69") (name "unconnected-(U4-INT1-Pad16)") (class "Default")
      (node (ref "U4") (pin "16") (pinfunction "INT1_16") (pintype "unspecified+no_connect"))
    )
    (net (code "70") (name "unconnected-(U4-INT2-Pad1)") (class "Default")
      (node (ref "U4") (pin "1") (pinfunction "INT2_1") (pintype "unspecified+no_connect"))
    )
    (net (code "71") (name "unconnected-(U4-INT3-Pad12)") (class "Default")
      (node (ref "U4") (pin "12") (pinfunction "INT3_12") (pintype "unspecified+no_connect"))
    )
    (net (code "72") (name "unconnected-(U4-INT4-Pad13)") (class "Default")
      (node (ref "U4") (pin "13") (pinfunction "INT4_13") (pintype "unspecified+no_connect"))
    )
    (net (code "73") (name "unconnected-(U6-VOUT-Pad4)") (class "Default")
      (node (ref "U6") (pin "4") (pinfunction "VOUT_4") (pintype "unspecified+no_connect"))
    )
    (net (code "74") (name "unconnected-(U8-DRDY-Pad8)") (class "Default")
      (node (ref "U8") (pin "8") (pinfunction "DRDY_8") (pintype "unspecified+no_connect"))
    )
    (net (code "75") (name "unconnected-(U8-INT-Pad7)") (class "Default")
      (node (ref "U8") (pin "7") (pinfunction "INT_7") (pintype "unspecified+no_connect"))
    )
    (net (code "76") (name "unconnected-(U10-CTS-Pad23)") (class "Default")
      (node (ref "U10") (pin "23") (pinfunction "CTS_23") (pintype "unspecified+no_connect"))
    )
    (net (code "77") (name "unconnected-(U10-DCD-Pad1)") (class "Default")
      (node (ref "U10") (pin "1") (pinfunction "DCD_1") (pintype "unspecified+no_connect"))
    )
    (net (code "78") (name "unconnected-(U10-DSR-Pad27)") (class "Default")
      (node (ref "U10") (pin "27") (pinfunction "DSR_27") (pintype "unspecified+no_connect"))
    )
    (net (code "79") (name "unconnected-(U10-NC-Pad10)") (class "Default")
      (node (ref "U10") (pin "10") (pinfunction "NC_10") (pintype "unspecified+no_connect"))
    )
    (net (code "80") (name "unconnected-(U10-NC-Pad13)") (class "Default")
      (node (ref "U10") (pin "13") (pinfunction "NC_13") (pintype "unspecified+no_connect"))
    )
    (net (code "81") (name "unconnected-(U10-NC-Pad14)") (class "Default")
      (node (ref "U10") (pin "14") (pinfunction "NC_14") (pintype "unspecified+no_connect"))
    )
    (net (code "82") (name "unconnected-(U10-NC-Pad15)") (class "Default")
      (node (ref "U10") (pin "15") (pinfunction "NC_15") (pintype "unspecified+no_connect"))
    )
    (net (code "83") (name "unconnected-(U10-NC-Pad16)") (class "Default")
      (node (ref "U10") (pin "16") (pinfunction "NC_16") (pintype "unspecified+no_connect"))
    )
    (net (code "84") (name "unconnected-(U10-NC-Pad17)") (class "Default")
      (node (ref "U10") (pin "17") (pinfunction "NC_17") (pintype "unspecified+no_connect"))
    )
    (net (code "85") (name "unconnected-(U10-NC-Pad18)") (class "Default")
      (node (ref "U10") (pin "18") (pinfunction "NC_18") (pintype "unspecified+no_connect"))
    )
    (net (code "86") (name "unconnected-(U10-NC-Pad19)") (class "Default")
      (node (ref "U10") (pin "19") (pinfunction "NC_19") (pintype "unspecified+no_connect"))
    )
    (net (code "87") (name "unconnected-(U10-NC-Pad20)") (class "Default")
      (node (ref "U10") (pin "20") (pinfunction "NC_20") (pintype "unspecified+no_connect"))
    )
    (net (code "88") (name "unconnected-(U10-NC-Pad21)") (class "Default")
      (node (ref "U10") (pin "21") (pinfunction "NC_21") (pintype "unspecified+no_connect"))
    )
    (net (code "89") (name "unconnected-(U10-NC-Pad22)") (class "Default")
      (node (ref "U10") (pin "22") (pinfunction "NC_22") (pintype "unspecified+no_connect"))
    )
    (net (code "90") (name "unconnected-(U10-RI-Pad2)") (class "Default")
      (node (ref "U10") (pin "2") (pinfunction "RI_2") (pintype "unspecified+no_connect"))
    )
    (net (code "91") (name "unconnected-(U10-SUSPEND#-Pad11)") (class "Default")
      (node (ref "U10") (pin "11") (pinfunction "SUSPEND#_11") (pintype "unspecified+no_connect"))
    )
    (net (code "92") (name "unconnected-(U10-SUSPEND-Pad12)") (class "Default")
      (node (ref "U10") (pin "12") (pinfunction "SUSPEND_12") (pintype "unspecified+no_connect"))
    )
    (net (code "93") (name "unconnected-(USB1-ID-Pad4)") (class "Default")
      (node (ref "USB1") (pin "4") (pinfunction "ID_4") (pintype "unspecified+no_connect"))
    )
  )
)
